# Switch_Matrix_Driver.net
KiCad netlist of a schematic drawn in Altium Designer
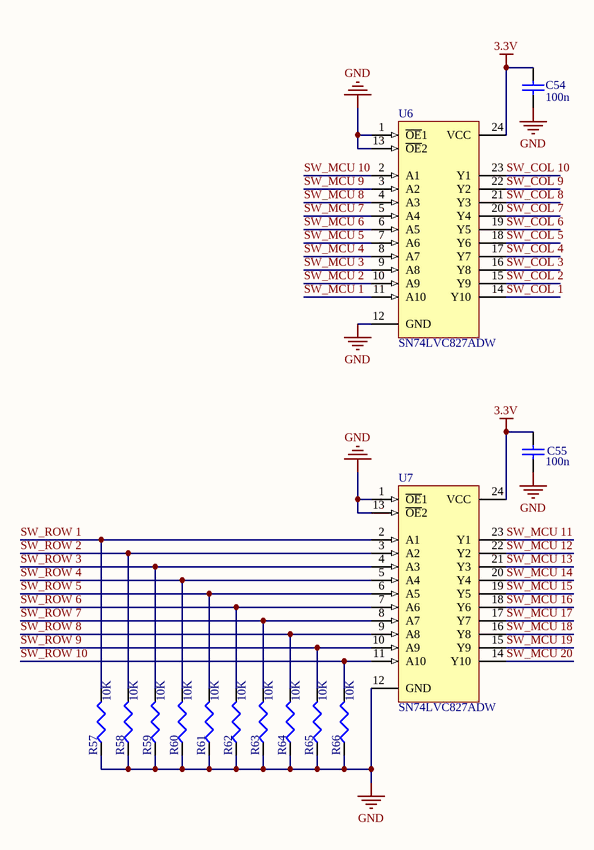
[diagram p0: Switch Matrix Driver.SchDoc]

(export (version "E")
  (design (tool "Eeschema 10.0.6"))
  (components
    (comp (ref "C54")
      (value "100n")
      (footprint "0805C-GENERIC")
      (description "Capacitor (Semiconductor SIM Model)")
      (fields (field (name "Comment") "Cap Semi") (field (name "PUBLISHER") "Altium Limited"))
      (libsource (lib "Miscellaneous Devices") (part "Cap Semi"))
    )
    (comp (ref "C55")
      (value "100n")
      (footprint "0805C-GENERIC")
      (description "Capacitor (Semiconductor SIM Model)")
      (fields (field (name "Comment") "Cap Semi") (field (name "PUBLISHER") "Altium Limited"))
      (libsource (lib "Miscellaneous Devices") (part "Cap Semi"))
    )
    (comp (ref "R57")
      (value "10K")
      (footprint "0805R-GENERIC")
      (description "Resistor")
      (fields (field (name "Comment") "Res3") (field (name "PUBLISHER") "Altium Limited"))
      (libsource (lib "Miscellaneous Devices") (part "Res3"))
    )
    (comp (ref "R58")
      (value "10K")
      (footprint "0805R-GENERIC")
      (description "Resistor")
      (fields (field (name "Comment") "Res3") (field (name "PUBLISHER") "Altium Limited"))
      (libsource (lib "Miscellaneous Devices") (part "Res3"))
    )
    (comp (ref "R59")
      (value "10K")
      (footprint "0805R-GENERIC")
      (description "Resistor")
      (fields (field (name "Comment") "Res3") (field (name "PUBLISHER") "Altium Limited"))
      (libsource (lib "Miscellaneous Devices") (part "Res3"))
    )
    (comp (ref "R60")
      (value "10K")
      (footprint "0805R-GENERIC")
      (description "Resistor")
      (fields (field (name "Comment") "Res3") (field (name "PUBLISHER") "Altium Limited"))
      (libsource (lib "Miscellaneous Devices") (part "Res3"))
    )
    (comp (ref "R61")
      (value "10K")
      (footprint "0805R-GENERIC")
      (description "Resistor")
      (fields (field (name "Comment") "Res3") (field (name "PUBLISHER") "Altium Limited"))
      (libsource (lib "Miscellaneous Devices") (part "Res3"))
    )
    (comp (ref "R62")
      (value "10K")
      (footprint "0805R-GENERIC")
      (description "Resistor")
      (fields (field (name "Comment") "Res3") (field (name "PUBLISHER") "Altium Limited"))
      (libsource (lib "Miscellaneous Devices") (part "Res3"))
    )
    (comp (ref "R63")
      (value "10K")
      (footprint "0805R-GENERIC")
      (description "Resistor")
      (fields (field (name "Comment") "Res3") (field (name "PUBLISHER") "Altium Limited"))
      (libsource (lib "Miscellaneous Devices") (part "Res3"))
    )
    (comp (ref "R64")
      (value "10K")
      (footprint "0805R-GENERIC")
      (description "Resistor")
      (fields (field (name "Comment") "Res3") (field (name "PUBLISHER") "Altium Limited"))
      (libsource (lib "Miscellaneous Devices") (part "Res3"))
    )
    (comp (ref "R65")
      (value "10K")
      (footprint "0805R-GENERIC")
      (description "Resistor")
      (fields (field (name "Comment") "Res3") (field (name "PUBLISHER") "Altium Limited"))
      (libsource (lib "Miscellaneous Devices") (part "Res3"))
    )
    (comp (ref "R66")
      (value "10K")
      (footprint "0805R-GENERIC")
      (description "Resistor")
      (fields (field (name "Comment") "Res3") (field (name "PUBLISHER") "Altium Limited"))
      (libsource (lib "Miscellaneous Devices") (part "Res3"))
    )
    (comp (ref "U6")
      (value "SN74LVC827ADW")
      (footprint "SOIC24")
      (description "10-Bit Buffer/Driver with 3-State Outputs")
      (fields (field (name "PUBLISHER") "Altium Limited"))
      (libsource (lib "TI Logic Buffer Line Driver") (part "SN74LVC827ADW"))
    )
    (comp (ref "U7")
      (value "SN74LVC827ADW")
      (footprint "SOIC24")
      (description "10-Bit Buffer/Driver with 3-State Outputs")
      (fields (field (name "PUBLISHER") "Altium Limited"))
      (libsource (lib "TI Logic Buffer Line Driver") (part "SN74LVC827ADW"))
    )
  )
  (nets
    (net (code "1") (name "/SW_COL 1") (class "Default")
      (node (ref "U6") (pin "14") (pinfunction "Y10_14") (pintype "tri_state"))
    )
    (net (code "2") (name "/SW_COL 2") (class "Default")
      (node (ref "U6") (pin "15") (pinfunction "Y9_15") (pintype "tri_state"))
    )
    (net (code "3") (name "/SW_COL 3") (class "Default")
      (node (ref "U6") (pin "16") (pinfunction "Y8_16") (pintype "tri_state"))
    )
    (net (code "4") (name "/SW_COL 4") (class "Default")
      (node (ref "U6") (pin "17") (pinfunction "Y7_17") (pintype "tri_state"))
    )
    (net (code "5") (name "/SW_COL 5") (class "Default")
      (node (ref "U6") (pin "18") (pinfunction "Y6_18") (pintype "tri_state"))
    )
    (net (code "6") (name "/SW_COL 6") (class "Default")
      (node (ref "U6") (pin "19") (pinfunction "Y5_19") (pintype "tri_state"))
    )
    (net (code "7") (name "/SW_COL 7") (class "Default")
      (node (ref "U6") (pin "20") (pinfunction "Y4_20") (pintype "tri_state"))
    )
    (net (code "8") (name "/SW_COL 8") (class "Default")
      (node (ref "U6") (pin "21") (pinfunction "Y3_21") (pintype "tri_state"))
    )
    (net (code "9") (name "/SW_COL 9") (class "Default")
      (node (ref "U6") (pin "22") (pinfunction "Y2_22") (pintype "tri_state"))
    )
    (net (code "10") (name "/SW_COL 10") (class "Default")
      (node (ref "U6") (pin "23") (pinfunction "Y1_23") (pintype "tri_state"))
    )
    (net (code "11") (name "/SW_MCU 1") (class "Default")
      (node (ref "U6") (pin "11") (pinfunction "A10_11") (pintype "input"))
    )
    (net (code "12") (name "/SW_MCU 2") (class "Default")
      (node (ref "U6") (pin "10") (pinfunction "A9_10") (pintype "input"))
    )
    (net (code "13") (name "/SW_MCU 3") (class "Default")
      (node (ref "U6") (pin "9") (pinfunction "A8_9") (pintype "input"))
    )
    (net (code "14") (name "/SW_MCU 4") (class "Default")
      (node (ref "U6") (pin "8") (pinfunction "A7_8") (pintype "input"))
    )
    (net (code "15") (name "/SW_MCU 5") (class "Default")
      (node (ref "U6") (pin "7") (pinfunction "A6_7") (pintype "input"))
    )
    (net (code "16") (name "/SW_MCU 6") (class "Default")
      (node (ref "U6") (pin "6") (pinfunction "A5_6") (pintype "input"))
    )
    (net (code "17") (name "/SW_MCU 7") (class "Default")
      (node (ref "U6") (pin "5") (pinfunction "A4_5") (pintype "input"))
    )
    (net (code "18") (name "/SW_MCU 8") (class "Default")
      (node (ref "U6") (pin "4") (pinfunction "A3_4") (pintype "input"))
    )
    (net (code "19") (name "/SW_MCU 9") (class "Default")
      (node (ref "U6") (pin "3") (pinfunction "A2_3") (pintype "input"))
    )
    (net (code "20") (name "/SW_MCU 10") (class "Default")
      (node (ref "U6") (pin "2") (pinfunction "A1_2") (pintype "input"))
    )
    (net (code "21") (name "/SW_MCU 11") (class "Default")
      (node (ref "U7") (pin "23") (pinfunction "Y1_23") (pintype "tri_state"))
    )
    (net (code "22") (name "/SW_MCU 12") (class "Default")
      (node (ref "U7") (pin "22") (pinfunction "Y2_22") (pintype "tri_state"))
    )
    (net (code "23") (name "/SW_MCU 13") (class "Default")
      (node (ref "U7") (pin "21") (pinfunction "Y3_21") (pintype "tri_state"))
    )
    (net (code "24") (name "/SW_MCU 14") (class "Default")
      (node (ref "U7") (pin "20") (pinfunction "Y4_20") (pintype "tri_state"))
    )
    (net (code "25") (name "/SW_MCU 15") (class "Default")
      (node (ref "U7") (pin "19") (pinfunction "Y5_19") (pintype "tri_state"))
    )
    (net (code "26") (name "/SW_MCU 16") (class "Default")
      (node (ref "U7") (pin "18") (pinfunction "Y6_18") (pintype "tri_state"))
    )
    (net (code "27") (name "/SW_MCU 17") (class "Default")
      (node (ref "U7") (pin "17") (pinfunction "Y7_17") (pintype "tri_state"))
    )
    (net (code "28") (name "/SW_MCU 18") (class "Default")
      (node (ref "U7") (pin "16") (pinfunction "Y8_16") (pintype "tri_state"))
    )
    (net (code "29") (name "/SW_MCU 19") (class "Default")
      (node (ref "U7") (pin "15") (pinfunction "Y9_15") (pintype "tri_state"))
    )
    (net (code "30") (name "/SW_MCU 20") (class "Default")
      (node (ref "U7") (pin "14") (pinfunction "Y10_14") (pintype "tri_state"))
    )
    (net (code "31") (name "/SW_ROW 1") (class "Default")
      (node (ref "R57") (pin "2") (pinfunction "2_2") (pintype "passive"))
      (node (ref "U7") (pin "2") (pinfunction "A1_2") (pintype "input"))
    )
    (net (code "32") (name "/SW_ROW 2") (class "Default")
      (node (ref "R58") (pin "2") (pinfunction "2_2") (pintype "passive"))
      (node (ref "U7") (pin "3") (pinfunction "A2_3") (pintype "input"))
    )
    (net (code "33") (name "/SW_ROW 3") (class "Default")
      (node (ref "R59") (pin "2") (pinfunction "2_2") (pintype "passive"))
      (node (ref "U7") (pin "4") (pinfunction "A3_4") (pintype "input"))
    )
    (net (code "34") (name "/SW_ROW 4") (class "Default")
      (node (ref "R60") (pin "2") (pinfunction "2_2") (pintype "passive"))
      (node (ref "U7") (pin "5") (pinfunction "A4_5") (pintype "input"))
    )
    (net (code "35") (name "/SW_ROW 5") (class "Default")
      (node (ref "R61") (pin "2") (pinfunction "2_2") (pintype "passive"))
      (node (ref "U7") (pin "6") (pinfunction "A5_6") (pintype "input"))
    )
    (net (code "36") (name "/SW_ROW 6") (class "Default")
      (node (ref "R62") (pin "2") (pinfunction "2_2") (pintype "passive"))
      (node (ref "U7") (pin "7") (pinfunction "A6_7") (pintype "input"))
    )
    (net (code "37") (name "/SW_ROW 7") (class "Default")
      (node (ref "R63") (pin "2") (pinfunction "2_2") (pintype "passive"))
      (node (ref "U7") (pin "8") (pinfunction "A7_8") (pintype "input"))
    )
    (net (code "38") (name "/SW_ROW 8") (class "Default")
      (node (ref "R64") (pin "2") (pinfunction "2_2") (pintype "passive"))
      (node (ref "U7") (pin "9") (pinfunction "A8_9") (pintype "input"))
    )
    (net (code "39") (name "/SW_ROW 9") (class "Default")
      (node (ref "R65") (pin "2") (pinfunction "2_2") (pintype "passive"))
      (node (ref "U7") (pin "10") (pinfunction "A9_10") (pintype "input"))
    )
    (net (code "40") (name "/SW_ROW 10") (class "Default")
      (node (ref "R66") (pin "2") (pinfunction "2_2") (pintype "passive"))
      (node (ref "U7") (pin "11") (pinfunction "A10_11") (pintype "input"))
    )
    (net (code "41") (name "3.3V") (class "Default")
      (node (ref "C54") (pin "2") (pinfunction "2_2") (pintype "passive"))
      (node (ref "C55") (pin "2") (pinfunction "2_2") (pintype "passive"))
      (node (ref "U6") (pin "24") (pinfunction "VCC_24") (pintype "power_in"))
      (node (ref "U7") (pin "24") (pinfunction "VCC_24") (pintype "power_in"))
    )
    (net (code "42") (name "GND") (class "Default")
      (node (ref "C54") (pin "1") (pinfunction "1_1") (pintype "passive"))
      (node (ref "C55") (pin "1") (pinfunction "1_1") (pintype "passive"))
      (node (ref "R57") (pin "1") (pinfunction "1_1") (pintype "passive"))
      (node (ref "R58") (pin "1") (pinfunction "1_1") (pintype "passive"))
      (node (ref "R59") (pin "1") (pinfunction "1_1") (pintype "passive"))
      (node (ref "R60") (pin "1") (pinfunction "1_1") (pintype "passive"))
      (node (ref "R61") (pin "1") (pinfunction "1_1") (pintype "passive"))
      (node (ref "R62") (pin "1") (pinfunction "1_1") (pintype "passive"))
      (node (ref "R63") (pin "1") (pinfunction "1_1") (pintype "passive"))
      (node (ref "R64") (pin "1") (pinfunction "1_1") (pintype "passive"))
      (node (ref "R65") (pin "1") (pinfunction "1_1") (pintype "passive"))
      (node (ref "R66") (pin "1") (pinfunction "1_1") (pintype "passive"))
      (node (ref "U6") (pin "1") (pinfunction "~{OE}1_1") (pintype "input"))
      (node (ref "U6") (pin "12") (pinfunction "GND_12") (pintype "power_in"))
      (node (ref "U6") (pin "13") (pinfunction "~{OE}2_13") (pintype "input"))
      (node (ref "U7") (pin "1") (pinfunction "~{OE}1_1") (pintype "input"))
      (node (ref "U7") (pin "12") (pinfunction "GND_12") (pintype "power_in"))
      (node (ref "U7") (pin "13") (pinfunction "~{OE}2_13") (pintype "input"))
    )
  )
)
